# SX1255.net
KiCad netlist of a schematic drawn in Altium Designer
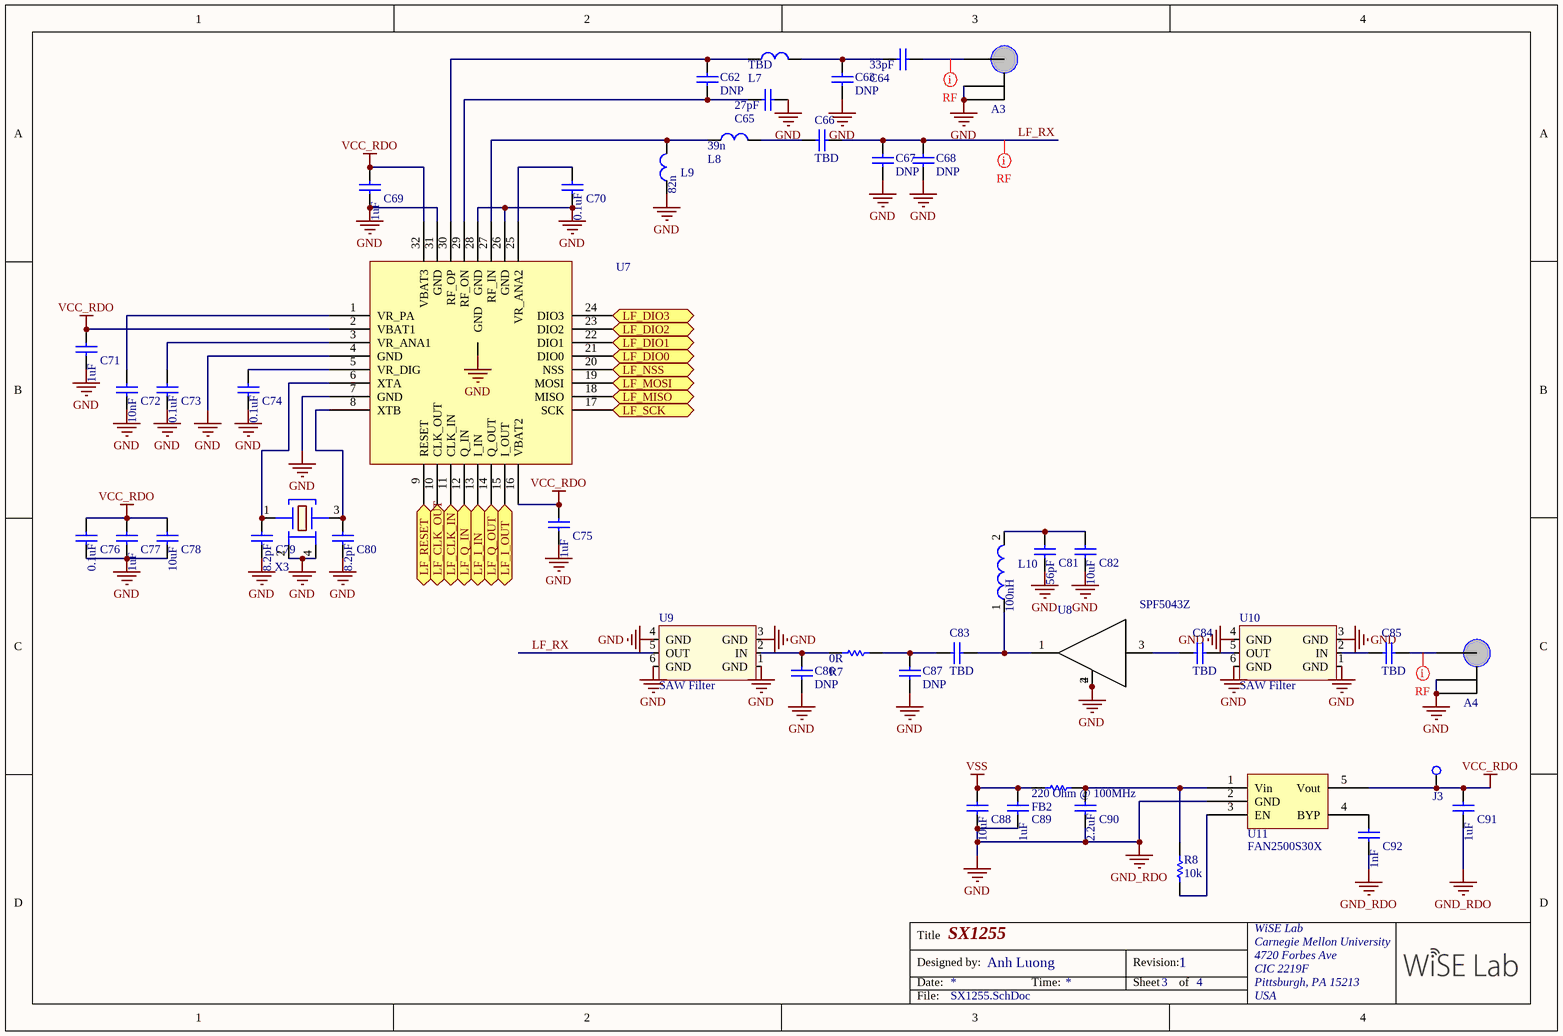
[diagram p0: SX1255.SchDoc]

(export (version "E")
  (design (tool "Eeschema 10.0.6"))
  (components
    (comp (ref "A3")
      (value "U.FL-R-SMT(01)")
      (footprint "U.FL-R-SMT-1")
      (description "CONN UMC JACK STR 50 OHM SMD")
      (fields (field (name "MANUFACTURER") "Hirose Electric Co Ltd"))
      (libsource (lib "Connectors") (part "U.FL-R-SMT(01)"))
    )
    (comp (ref "A4")
      (value "U.FL-R-SMT(01)")
      (footprint "U.FL-R-SMT-1")
      (description "CONN UMC JACK STR 50 OHM SMD")
      (fields (field (name "MANUFACTURER") "Hirose Electric Co Ltd"))
      (libsource (lib "Connectors") (part "U.FL-R-SMT(01)"))
    )
    (comp (ref "C62")
      (value "DNP")
      (footprint "CAPC1005X04L")
      (description "C_DNP")
      (libsource (lib "Passives") (part "C_DNP"))
    )
    (comp (ref "C63")
      (value "DNP")
      (footprint "CAPC1005X04L")
      (description "C_DNP")
      (libsource (lib "Passives") (part "C_DNP"))
    )
    (comp (ref "C64")
      (value "GRM1555C1H330JA01D")
      (footprint "CAPC1005X04L")
      (description "CAP CER 33PF 50V C0G/NP0 0402")
      (fields
        (field (name "MANUFACTURER") "Murata Electronics North America")
        (field (name "TOLERANCE") "±5%")
      )
      (libsource (lib "Passives") (part "GRM1555C1H330JA01D"))
    )
    (comp (ref "C65")
      (value "GRM1555C1H270JA01J")
      (footprint "CAPC1005X04L")
      (description "CAP CER 27PF 50V C0G/NP0 0402")
      (fields
        (field (name "MANUFACTURER") "Murata Electronics North America")
        (field (name "TOLERANCE") "±5%")
      )
      (libsource (lib "Passives") (part "GRM1555C1H270JA01J"))
    )
    (comp (ref "C66")
      (value "TBD")
      (footprint "CAPC1005X04L")
      (description "C_TBD")
      (libsource (lib "Passives") (part "C_TBD"))
    )
    (comp (ref "C67")
      (value "DNP")
      (footprint "CAPC1005X04L")
      (description "C_DNP")
      (libsource (lib "Passives") (part "C_DNP"))
    )
    (comp (ref "C68")
      (value "DNP")
      (footprint "CAPC1005X04L")
      (description "C_DNP")
      (libsource (lib "Passives") (part "C_DNP"))
    )
    (comp (ref "C69")
      (value "GRM155R60J105KE19D")
      (footprint "CAPC1005X04L")
      (description "CAP CER 1UF 6.3V X5R 0402")
      (fields
        (field (name "MANUFACTURER") "Murata Electronics North America")
        (field (name "TOLERANCE") "±10%")
      )
      (libsource (lib "Passives") (part "GRM155R60J105KE19D"))
    )
    (comp (ref "C70")
      (value "GRM155R71C104KA88D")
      (footprint "CAPC1005X04L")
      (description "CAP CER 0.1UF 16V X7R 0402")
      (fields
        (field (name "MANUFACTURER") "Murata Electronics North America")
        (field (name "TOLERANCE") "±10%")
      )
      (libsource (lib "Passives") (part "GRM155R71C104KA88D"))
    )
    (comp (ref "C71")
      (value "GRM155R60J105KE19D")
      (footprint "CAPC1005X04L")
      (description "CAP CER 1UF 6.3V X5R 0402")
      (fields
        (field (name "MANUFACTURER") "Murata Electronics North America")
        (field (name "TOLERANCE") "±10%")
      )
      (libsource (lib "Passives") (part "GRM155R60J105KE19D"))
    )
    (comp (ref "C72")
      (value "GRM155R71E103KA01D")
      (footprint "CAPC1005X04L")
      (description "CAP CER 10000PF 25V X7R 0402")
      (fields
        (field (name "MANUFACTURER") "Murata Electronics North America")
        (field (name "TOLERANCE") "±10%")
      )
      (libsource (lib "Passives") (part "GRM155R71E103KA01D"))
    )
    (comp (ref "C73")
      (value "GRM155R71C104KA88D")
      (footprint "CAPC1005X04L")
      (description "CAP CER 0.1UF 16V X7R 0402")
      (fields
        (field (name "MANUFACTURER") "Murata Electronics North America")
        (field (name "TOLERANCE") "±10%")
      )
      (libsource (lib "Passives") (part "GRM155R71C104KA88D"))
    )
    (comp (ref "C74")
      (value "GRM155R71C104KA88D")
      (footprint "CAPC1005X04L")
      (description "CAP CER 0.1UF 16V X7R 0402")
      (fields
        (field (name "MANUFACTURER") "Murata Electronics North America")
        (field (name "TOLERANCE") "±10%")
      )
      (libsource (lib "Passives") (part "GRM155R71C104KA88D"))
    )
    (comp (ref "C75")
      (value "GRM155R60J105KE19D")
      (footprint "CAPC1005X04L")
      (description "CAP CER 1UF 6.3V X5R 0402")
      (fields
        (field (name "MANUFACTURER") "Murata Electronics North America")
        (field (name "TOLERANCE") "±10%")
      )
      (libsource (lib "Passives") (part "GRM155R60J105KE19D"))
    )
    (comp (ref "C76")
      (value "GRM155R71C104KA88D")
      (footprint "CAPC1005X04L")
      (description "CAP CER 0.1UF 16V X7R 0402")
      (fields
        (field (name "MANUFACTURER") "Murata Electronics North America")
        (field (name "TOLERANCE") "±10%")
      )
      (libsource (lib "Passives") (part "GRM155R71C104KA88D"))
    )
    (comp (ref "C77")
      (value "GRM155R60J105KE19D")
      (footprint "CAPC1005X04L")
      (description "CAP CER 1UF 6.3V X5R 0402")
      (fields
        (field (name "MANUFACTURER") "Murata Electronics North America")
        (field (name "TOLERANCE") "±10%")
      )
      (libsource (lib "Passives") (part "GRM155R60J105KE19D"))
    )
    (comp (ref "C78")
      (value "GRM155R60J106ME15D")
      (footprint "INDC1005X04L")
      (description "CAP CER 10UF 6.3V X5R 0402")
      (fields
        (field (name "MANUFACTURER") "Murata Electronics North America")
        (field (name "TOLERANCE") "±20%")
      )
      (libsource (lib "Passives") (part "GRM155R60J106ME15D"))
    )
    (comp (ref "C79")
      (value "GRM1555C1H8R2CA01D")
      (footprint "CAPC1005X04L")
      (description "CAP CER 8.2PF 50V C0G/NP0 0402")
      (fields
        (field (name "MANUFACTURER") "Murata Electronics North America")
        (field (name "TOLERANCE") "±0.25pF")
      )
      (libsource (lib "Passives") (part "GRM1555C1H8R2CA01D"))
    )
    (comp (ref "C80")
      (value "GRM1555C1H8R2CA01D")
      (footprint "CAPC1005X04L")
      (description "CAP CER 8.2PF 50V C0G/NP0 0402")
      (fields
        (field (name "MANUFACTURER") "Murata Electronics North America")
        (field (name "TOLERANCE") "±0.25pF")
      )
      (libsource (lib "Passives") (part "GRM1555C1H8R2CA01D"))
    )
    (comp (ref "C81")
      (value "GRM1555C1H560JA01D")
      (footprint "CAPC1005X04L")
      (description "CAP CER 56PF 50V C0G/NP0 0402")
      (fields
        (field (name "MANUFACTURER") "Murata Electronics North America")
        (field (name "TOLERANCE") "±5%")
      )
      (libsource (lib "Passives") (part "GRM1555C1H560JA01D"))
    )
    (comp (ref "C82")
      (value "GRM155R60J106ME15D")
      (footprint "INDC1005X04L")
      (description "CAP CER 10UF 6.3V X5R 0402")
      (fields
        (field (name "MANUFACTURER") "Murata Electronics North America")
        (field (name "TOLERANCE") "±20%")
      )
      (libsource (lib "Passives") (part "GRM155R60J106ME15D"))
    )
    (comp (ref "C83")
      (value "TBD")
      (footprint "CAPC1005X04L")
      (description "C_TBD")
      (libsource (lib "Passives") (part "C_TBD"))
    )
    (comp (ref "C84")
      (value "TBD")
      (footprint "CAPC1005X04L")
      (description "C_TBD")
      (libsource (lib "Passives") (part "C_TBD"))
    )
    (comp (ref "C85")
      (value "TBD")
      (footprint "CAPC1005X04L")
      (description "C_TBD")
      (libsource (lib "Passives") (part "C_TBD"))
    )
    (comp (ref "C86")
      (value "DNP")
      (footprint "CAPC1005X04L")
      (description "C_DNP")
      (libsource (lib "Passives") (part "C_DNP"))
    )
    (comp (ref "C87")
      (value "DNP")
      (footprint "CAPC1005X04L")
      (description "C_DNP")
      (libsource (lib "Passives") (part "C_DNP"))
    )
    (comp (ref "C88")
      (value "GRM188C81C106MA73D")
      (footprint "CAPC1608X08N (0603)")
      (description "CAP CER 10UF 16V 20% X6S 0603")
      (fields
        (field (name "MANUFACTURER") "Murata Electronics North America")
        (field (name "TOLERANCE") "±20%")
      )
      (libsource (lib "Chronos") (part "GRM188C81C106MA73D"))
    )
    (comp (ref "C89")
      (value "GRM188R61A105KA61D")
      (footprint "CAPC1608X08N (0603)")
      (description "CAP CER 1UF 10V 10% X5R 0603")
      (fields
        (field (name "MANUFACTURER") "Murata Electronics North America")
        (field (name "TOLERANCE") "±10%")
      )
      (libsource (lib "Chronos") (part "GRM188R61A105KA61D"))
    )
    (comp (ref "C90")
      (value "GRM188R60J225KE19D")
      (footprint "CAPC1608X08N (0603)")
      (description "CAP CER 2.2UF 6.3V 10% X5R 0603")
      (fields
        (field (name "MANUFACTURER") "Murata Electronics North America")
        (field (name "TOLERANCE") "±10%")
      )
      (libsource (lib "Chronos") (part "GRM188R60J225KE19D"))
    )
    (comp (ref "C91")
      (value "GRM188R61A105KA61D")
      (footprint "CAPC1608X08N (0603)")
      (description "CAP CER 1UF 10V 10% X5R 0603")
      (fields
        (field (name "MANUFACTURER") "Murata Electronics North America")
        (field (name "TOLERANCE") "±10%")
      )
      (libsource (lib "Chronos") (part "GRM188R61A105KA61D"))
    )
    (comp (ref "C92")
      (value "GRM1885C1H102JA01D")
      (footprint "CAPC1608X08N (0603)")
      (description "CAP CER 1000PF 50V 5% NP0 0603")
      (fields
        (field (name "MANUFACTURER") "Murata Electronics North America")
        (field (name "TOLERANCE") "±5%")
      )
      (libsource (lib "Chronos") (part "GRM1885C1H102JA01D"))
    )
    (comp (ref "FB2")
      (value "BLM18BD221SN1D")
      (footprint "RESC1608X06N (0603)")
      (description "FERRITE CHIP 220 OHM 200MA 0603")
      (fields (field (name "MANUFACTURER") "Murata Electronics North America"))
      (libsource (lib "Chronos") (part "BLM18BD221SN1D"))
    )
    (comp (ref "J3")
      (value "5004")
      (footprint "TP")
      (description "TEST POINT PC MINI .040\"D YELLOW")
      (fields (field (name "MANUFACTURER") "Keystone Electronics"))
      (libsource (lib "Chronos") (part "5004"))
    )
    (comp (ref "L7") (value "L_TBD") (footprint "INDC1005X04L") (libsource (lib "Passives") (part "L_TBD")))
    (comp (ref "L8")
      (value "LQG15HS39NJ02D")
      (footprint "INDC1005X04L")
      (description "FIXED IND 39NH 300MA 650 MOHM")
      (fields
        (field (name "MANUFACTURER") "Murata Electronics North America")
        (field (name "TOLERANCE") "±5%")
      )
      (libsource (lib "Passives") (part "LQG15HS39NJ02D"))
    )
    (comp (ref "L9")
      (value "LQG15HS82NJ02D")
      (footprint "INDC1005X04L")
      (description "FIXED IND 82NH 200MA 1.2 OHM SMD")
      (fields
        (field (name "MANUFACTURER") "Murata Electronics North America")
        (field (name "TOLERANCE") "±5%")
      )
      (libsource (lib "Passives") (part "LQG15HS82NJ02D"))
    )
    (comp (ref "L10")
      (value "LQG15HSR10J02D")
      (footprint "INDC1005X04L")
      (description "FIXED IND 100NH 200MA 1.25 OHM")
      (fields
        (field (name "MANUFACTURER") "Murata Electronics North America")
        (field (name "TOLERANCE") "±5%")
      )
      (libsource (lib "Passives") (part "LQG15HSR10J02D"))
    )
    (comp (ref "R7")
      (value "PMR01ZZPJ000")
      (footprint "RESC1005X04N")
      (description "RES SMD 0 OHM JUMPER 1/5W 0402")
      (fields (field (name "MANUFACTURER") "Rohm Semiconductor") (field (name "TOLERANCE") "Jumper"))
      (libsource (lib "Passives") (part "PMR01ZZPJ000"))
    )
    (comp (ref "R8")
      (value "10k")
      (footprint "RESC1608X06N (0603)")
      (description "RES SMD 10K OHM 1% 1/10W 0603")
      (fields
        (field (name "MANUFACTURER") "Rohm Semiconductor")
        (field (name "MANUFACTURER PART NUMBER") "MCR03ERTF1002")
      )
      (libsource (lib "Chronos") (part "MCR03ERTF1002"))
    )
    (comp (ref "U7")
      (value "SX1257IWLTRT")
      (footprint "QFN50P500X500X80_HS-33N")
      (description "IC RF TXRX 802.15.4 32WFQFN")
      (fields (field (name "MANUFACTURER") "Semtech Corporation"))
      (libsource (lib "RFIC") (part "SX1257IWLTRT"))
    )
    (comp (ref "U8")
      (value "SPF5043Z")
      (footprint "SOT-343")
      (description "SPF5043Z; Low Noise Amplifier; RFMD")
      (fields (field (name "MANUFACTURER") "RFMD"))
      (libsource (lib "RFIC") (part "SPF5043Z"))
    )
    (comp (ref "U9")
      (value "SAW Filter")
      (footprint "DCC6C_3.0x3.0mm")
      (description "SAW Filter - Bandpass - TEMEX type")
      (libsource (lib "RFIC") (part "SAW Filter"))
    )
    (comp (ref "U10")
      (value "SAW Filter")
      (footprint "DCC6C_3.0x3.0mm")
      (description "SAW Filter - Bandpass - TEMEX type")
      (libsource (lib "RFIC") (part "SAW Filter"))
    )
    (comp (ref "U11")
      (value "FAN2500S30X")
      (footprint "SOT95P280X145-5N")
      (description "IC REG LDO 3V 0.1A SOT23-5")
      (fields (field (name "MANUFACTURER") "Fairchild Semiconductor"))
      (libsource (lib "Chronos") (part "FAN2500S30X"))
    )
    (comp (ref "X3")
      (value "ABM11-36.000MHZ-D2X-T3")
      (footprint "2.0x1.6x0.59mmXTAL")
      (description "CRYSTAL 36.0000MHZ 10PF SMD")
      (fields (field (name "MANUFACTURER") "Abracon LLC"))
      (libsource (lib "OSC") (part "ABM11-36.000MHZ-D2X-T3"))
    )
  )
  (nets
    (net (code "1") (name "/LF_CLK_IN") (class "Default")
      (node (ref "U7") (pin "11") (pinfunction "CLK_IN_11") (pintype "passive"))
    )
    (net (code "2") (name "/LF_CLK_OUT") (class "Default")
      (node (ref "U7") (pin "10") (pinfunction "CLK_OUT_10") (pintype "passive"))
    )
    (net (code "3") (name "/LF_DIO0") (class "Default")
      (node (ref "U7") (pin "21") (pinfunction "DIO0_21") (pintype "passive"))
    )
    (net (code "4") (name "/LF_DIO1") (class "Default")
      (node (ref "U7") (pin "22") (pinfunction "DIO1_22") (pintype "passive"))
    )
    (net (code "5") (name "/LF_DIO2") (class "Default")
      (node (ref "U7") (pin "23") (pinfunction "DIO2_23") (pintype "passive"))
    )
    (net (code "6") (name "/LF_DIO3") (class "Default")
      (node (ref "U7") (pin "24") (pinfunction "DIO3_24") (pintype "passive"))
    )
    (net (code "7") (name "/LF_I_IN") (class "Default")
      (node (ref "U7") (pin "13") (pinfunction "I_IN_13") (pintype "passive"))
    )
    (net (code "8") (name "/LF_I_OUT") (class "Default")
      (node (ref "U7") (pin "15") (pinfunction "I_OUT_15") (pintype "passive"))
    )
    (net (code "9") (name "/LF_MISO") (class "Default")
      (node (ref "U7") (pin "18") (pinfunction "MISO_18") (pintype "passive"))
    )
    (net (code "10") (name "/LF_MOSI") (class "Default")
      (node (ref "U7") (pin "19") (pinfunction "MOSI_19") (pintype "passive"))
    )
    (net (code "11") (name "/LF_NSS") (class "Default")
      (node (ref "U7") (pin "20") (pinfunction "NSS_20") (pintype "passive"))
    )
    (net (code "12") (name "/LF_Q_IN") (class "Default")
      (node (ref "U7") (pin "12") (pinfunction "Q_IN_12") (pintype "passive"))
    )
    (net (code "13") (name "/LF_Q_OUT") (class "Default")
      (node (ref "U7") (pin "14") (pinfunction "Q_OUT_14") (pintype "passive"))
    )
    (net (code "14") (name "/LF_RESET") (class "Default")
      (node (ref "U7") (pin "9") (pinfunction "RESET_9") (pintype "passive"))
    )
    (net (code "15") (name "/LF_RX") (class "Default")
      (node (ref "C66") (pin "2") (pinfunction "2_2") (pintype "passive"))
      (node (ref "C67") (pin "2") (pinfunction "2_2") (pintype "passive"))
      (node (ref "C68") (pin "2") (pinfunction "2_2") (pintype "passive"))
      (node (ref "U9") (pin "5") (pinfunction "OUT_5") (pintype "passive"))
    )
    (net (code "16") (name "/LF_SCK") (class "Default")
      (node (ref "U7") (pin "17") (pinfunction "SCK_17") (pintype "passive"))
    )
    (net (code "17") (name "GND") (class "Default")
      (node (ref "A3") (pin "2") (pinfunction "2_2") (pintype "passive"))
      (node (ref "A3") (pin "3") (pinfunction "3_3") (pintype "passive"))
      (node (ref "A4") (pin "2") (pinfunction "2_2") (pintype "passive"))
      (node (ref "A4") (pin "3") (pinfunction "3_3") (pintype "passive"))
      (node (ref "C63") (pin "1") (pinfunction "1_1") (pintype "passive"))
      (node (ref "C65") (pin "2") (pinfunction "2_2") (pintype "passive"))
      (node (ref "C67") (pin "1") (pinfunction "1_1") (pintype "passive"))
      (node (ref "C68") (pin "1") (pinfunction "1_1") (pintype "passive"))
      (node (ref "C69") (pin "1") (pinfunction "1_1") (pintype "passive"))
      (node (ref "C70") (pin "1") (pinfunction "1_1") (pintype "passive"))
      (node (ref "C71") (pin "1") (pinfunction "1_1") (pintype "passive"))
      (node (ref "C72") (pin "1") (pinfunction "1_1") (pintype "passive"))
      (node (ref "C73") (pin "1") (pinfunction "1_1") (pintype "passive"))
      (node (ref "C74") (pin "1") (pinfunction "1_1") (pintype "passive"))
      (node (ref "C75") (pin "1") (pinfunction "1_1") (pintype "passive"))
      (node (ref "C76") (pin "1") (pinfunction "1_1") (pintype "passive"))
      (node (ref "C77") (pin "1") (pinfunction "1_1") (pintype "passive"))
      (node (ref "C78") (pin "1") (pinfunction "1_1") (pintype "passive"))
      (node (ref "C79") (pin "1") (pinfunction "1_1") (pintype "passive"))
      (node (ref "C80") (pin "1") (pinfunction "1_1") (pintype "passive"))
      (node (ref "C81") (pin "1") (pinfunction "1_1") (pintype "passive"))
      (node (ref "C82") (pin "1") (pinfunction "1_1") (pintype "passive"))
      (node (ref "C86") (pin "1") (pinfunction "1_1") (pintype "passive"))
      (node (ref "C87") (pin "1") (pinfunction "1_1") (pintype "passive"))
      (node (ref "C88") (pin "1") (pinfunction "1_1") (pintype "passive"))
      (node (ref "C89") (pin "1") (pinfunction "1_1") (pintype "passive"))
      (node (ref "C90") (pin "1") (pinfunction "1_1") (pintype "passive"))
      (node (ref "C91") (pin "1") (pinfunction "1_1") (pintype "passive"))
      (node (ref "C92") (pin "1") (pinfunction "1_1") (pintype "passive"))
      (node (ref "L9") (pin "1") (pinfunction "1_1") (pintype "passive"))
      (node (ref "U10") (pin "1") (pinfunction "GND_1") (pintype "passive"))
      (node (ref "U10") (pin "3") (pinfunction "GND_3") (pintype "passive"))
      (node (ref "U10") (pin "4") (pinfunction "GND_4") (pintype "passive"))
      (node (ref "U10") (pin "6") (pinfunction "GND_6") (pintype "passive"))
      (node (ref "U11") (pin "2") (pinfunction "GND_2") (pintype "passive"))
      (node (ref "U7") (pin "26") (pinfunction "GND_26") (pintype "passive"))
      (node (ref "U7") (pin "28") (pinfunction "GND_28") (pintype "passive"))
      (node (ref "U7") (pin "31") (pinfunction "GND_31") (pintype "passive"))
      (node (ref "U7") (pin "33") (pinfunction "GND_33") (pintype "passive"))
      (node (ref "U7") (pin "4") (pinfunction "GND_4") (pintype "passive"))
      (node (ref "U7") (pin "7") (pinfunction "GND_7") (pintype "passive"))
      (node (ref "U8") (pin "2") (pinfunction "GND1_2") (pintype "passive"))
      (node (ref "U8") (pin "4") (pinfunction "GND2_4") (pintype "passive"))
      (node (ref "U9") (pin "1") (pinfunction "GND_1") (pintype "passive"))
      (node (ref "U9") (pin "3") (pinfunction "GND_3") (pintype "passive"))
      (node (ref "U9") (pin "4") (pinfunction "GND_4") (pintype "passive"))
      (node (ref "U9") (pin "6") (pinfunction "GND_6") (pintype "passive"))
      (node (ref "X3") (pin "2") (pinfunction "2_2") (pintype "power_in"))
      (node (ref "X3") (pin "4") (pinfunction "4_4") (pintype "power_in"))
    )
    (net (code "18") (name "Net-(A3-Pad1)") (class "Default")
      (node (ref "A3") (pin "1") (pinfunction "1_1") (pintype "passive"))
      (node (ref "C64") (pin "2") (pinfunction "2_2") (pintype "passive"))
    )
    (net (code "19") (name "Net-(A4-Pad1)") (class "Default")
      (node (ref "A4") (pin "1") (pinfunction "1_1") (pintype "passive"))
      (node (ref "C85") (pin "2") (pinfunction "2_2") (pintype "passive"))
    )
    (net (code "20") (name "Net-(C63-Pad2)") (class "Default")
      (node (ref "C63") (pin "2") (pinfunction "2_2") (pintype "passive"))
      (node (ref "C64") (pin "1") (pinfunction "1_1") (pintype "passive"))
      (node (ref "L7") (pin "2") (pinfunction "2_2") (pintype "passive"))
    )
    (net (code "21") (name "Net-(C66-Pad1)") (class "Default")
      (node (ref "C66") (pin "1") (pinfunction "1_1") (pintype "passive"))
      (node (ref "L8") (pin "2") (pinfunction "2_2") (pintype "passive"))
    )
    (net (code "22") (name "Net-(C81-Pad2)") (class "Default")
      (node (ref "C81") (pin "2") (pinfunction "2_2") (pintype "passive"))
      (node (ref "C82") (pin "2") (pinfunction "2_2") (pintype "passive"))
      (node (ref "L10") (pin "2") (pinfunction "2_2") (pintype "passive"))
    )
    (net (code "23") (name "Net-(C83-Pad1)") (class "Default")
      (node (ref "C83") (pin "1") (pinfunction "1_1") (pintype "passive"))
      (node (ref "C87") (pin "2") (pinfunction "2_2") (pintype "passive"))
      (node (ref "R7") (pin "2") (pinfunction "2_2") (pintype "passive"))
    )
    (net (code "24") (name "Net-(U7-RF_IN)") (class "Default")
      (node (ref "L8") (pin "1") (pinfunction "1_1") (pintype "passive"))
      (node (ref "L9") (pin "2") (pinfunction "2_2") (pintype "passive"))
      (node (ref "U7") (pin "27") (pinfunction "RF_IN_27") (pintype "passive"))
    )
    (net (code "25") (name "Net-(U7-RF_ON)") (class "Default")
      (node (ref "C62") (pin "1") (pinfunction "1_1") (pintype "passive"))
      (node (ref "C65") (pin "1") (pinfunction "1_1") (pintype "passive"))
      (node (ref "U7") (pin "29") (pinfunction "RF_ON_29") (pintype "passive"))
    )
    (net (code "26") (name "Net-(U7-RF_OP)") (class "Default")
      (node (ref "C62") (pin "2") (pinfunction "2_2") (pintype "passive"))
      (node (ref "L7") (pin "1") (pinfunction "1_1") (pintype "passive"))
      (node (ref "U7") (pin "30") (pinfunction "RF_OP_30") (pintype "passive"))
    )
    (net (code "27") (name "Net-(U7-VR_ANA1)") (class "Default")
      (node (ref "C73") (pin "2") (pinfunction "2_2") (pintype "passive"))
      (node (ref "U7") (pin "3") (pinfunction "VR_ANA1_3") (pintype "passive"))
    )
    (net (code "28") (name "Net-(U7-VR_ANA2)") (class "Default")
      (node (ref "C70") (pin "2") (pinfunction "2_2") (pintype "passive"))
      (node (ref "U7") (pin "25") (pinfunction "VR_ANA2_25") (pintype "passive"))
    )
    (net (code "29") (name "Net-(U7-VR_DIG)") (class "Default")
      (node (ref "C74") (pin "2") (pinfunction "2_2") (pintype "passive"))
      (node (ref "U7") (pin "5") (pinfunction "VR_DIG_5") (pintype "passive"))
    )
    (net (code "30") (name "Net-(U7-VR_PA)") (class "Default")
      (node (ref "C72") (pin "2") (pinfunction "2_2") (pintype "passive"))
      (node (ref "U7") (pin "1") (pinfunction "VR_PA_1") (pintype "passive"))
    )
    (net (code "31") (name "Net-(U7-XTA)") (class "Default")
      (node (ref "C79") (pin "2") (pinfunction "2_2") (pintype "passive"))
      (node (ref "U7") (pin "6") (pinfunction "XTA_6") (pintype "passive"))
      (node (ref "X3") (pin "1") (pinfunction "1_1") (pintype "passive"))
    )
    (net (code "32") (name "Net-(U7-XTB)") (class "Default")
      (node (ref "C80") (pin "2") (pinfunction "2_2") (pintype "passive"))
      (node (ref "U7") (pin "8") (pinfunction "XTB_8") (pintype "passive"))
      (node (ref "X3") (pin "3") (pinfunction "3_3") (pintype "passive"))
    )
    (net (code "33") (name "Net-(U8-IN)") (class "Default")
      (node (ref "C84") (pin "1") (pinfunction "1_1") (pintype "passive"))
      (node (ref "U8") (pin "3") (pinfunction "IN_3") (pintype "passive"))
    )
    (net (code "34") (name "Net-(U8-OUT)") (class "Default")
      (node (ref "C83") (pin "2") (pinfunction "2_2") (pintype "passive"))
      (node (ref "L10") (pin "1") (pinfunction "1_1") (pintype "passive"))
      (node (ref "U8") (pin "1") (pinfunction "OUT_1") (pintype "passive"))
    )
    (net (code "35") (name "Net-(U9-IN)") (class "Default")
      (node (ref "C86") (pin "2") (pinfunction "2_2") (pintype "passive"))
      (node (ref "R7") (pin "1") (pinfunction "1_1") (pintype "passive"))
      (node (ref "U9") (pin "2") (pinfunction "IN_2") (pintype "passive"))
    )
    (net (code "36") (name "Net-(U10-IN)") (class "Default")
      (node (ref "C85") (pin "1") (pinfunction "1_1") (pintype "passive"))
      (node (ref "U10") (pin "2") (pinfunction "IN_2") (pintype "passive"))
    )
    (net (code "37") (name "Net-(U10-OUT)") (class "Default")
      (node (ref "C84") (pin "2") (pinfunction "2_2") (pintype "passive"))
      (node (ref "U10") (pin "5") (pinfunction "OUT_5") (pintype "passive"))
    )
    (net (code "38") (name "Net-(U11-BYP)") (class "Default")
      (node (ref "C92") (pin "2") (pinfunction "2_2") (pintype "passive"))
      (node (ref "U11") (pin "4") (pinfunction "BYP_4") (pintype "passive"))
    )
    (net (code "39") (name "Net-(U11-EN)") (class "Default")
      (node (ref "R8") (pin "1") (pinfunction "1_1") (pintype "passive"))
      (node (ref "U11") (pin "3") (pinfunction "EN_3") (pintype "passive"))
    )
    (net (code "40") (name "Net-(U11-Vin)") (class "Default")
      (node (ref "C90") (pin "2") (pinfunction "2_2") (pintype "passive"))
      (node (ref "FB2") (pin "2") (pinfunction "2_2") (pintype "passive"))
      (node (ref "R8") (pin "2") (pinfunction "2_2") (pintype "passive"))
      (node (ref "U11") (pin "1") (pinfunction "Vin_1") (pintype "passive"))
    )
    (net (code "41") (name "VCC_RDO") (class "Default")
      (node (ref "C69") (pin "2") (pinfunction "2_2") (pintype "passive"))
      (node (ref "C71") (pin "2") (pinfunction "2_2") (pintype "passive"))
      (node (ref "C75") (pin "2") (pinfunction "2_2") (pintype "passive"))
      (node (ref "C76") (pin "2") (pinfunction "2_2") (pintype "passive"))
      (node (ref "C77") (pin "2") (pinfunction "2_2") (pintype "passive"))
      (node (ref "C78") (pin "2") (pinfunction "2_2") (pintype "passive"))
      (node (ref "C91") (pin "2") (pinfunction "2_2") (pintype "passive"))
      (node (ref "J3") (pin "1") (pinfunction "1_1") (pintype "passive"))
      (node (ref "U11") (pin "5") (pinfunction "Vout_5") (pintype "passive"))
      (node (ref "U7") (pin "16") (pinfunction "VBAT2_16") (pintype "passive"))
      (node (ref "U7") (pin "2") (pinfunction "VBAT1_2") (pintype "passive"))
      (node (ref "U7") (pin "32") (pinfunction "VBAT3_32") (pintype "passive"))
    )
    (net (code "42") (name "VSS") (class "Default")
      (node (ref "C88") (pin "2") (pinfunction "2_2") (pintype "passive"))
      (node (ref "C89") (pin "2") (pinfunction "2_2") (pintype "passive"))
      (node (ref "FB2") (pin "1") (pinfunction "1_1") (pintype "passive"))
    )
  )
)
